# OBC_v1_rev_d.net
KiCad netlist of a schematic drawn in EAGLE
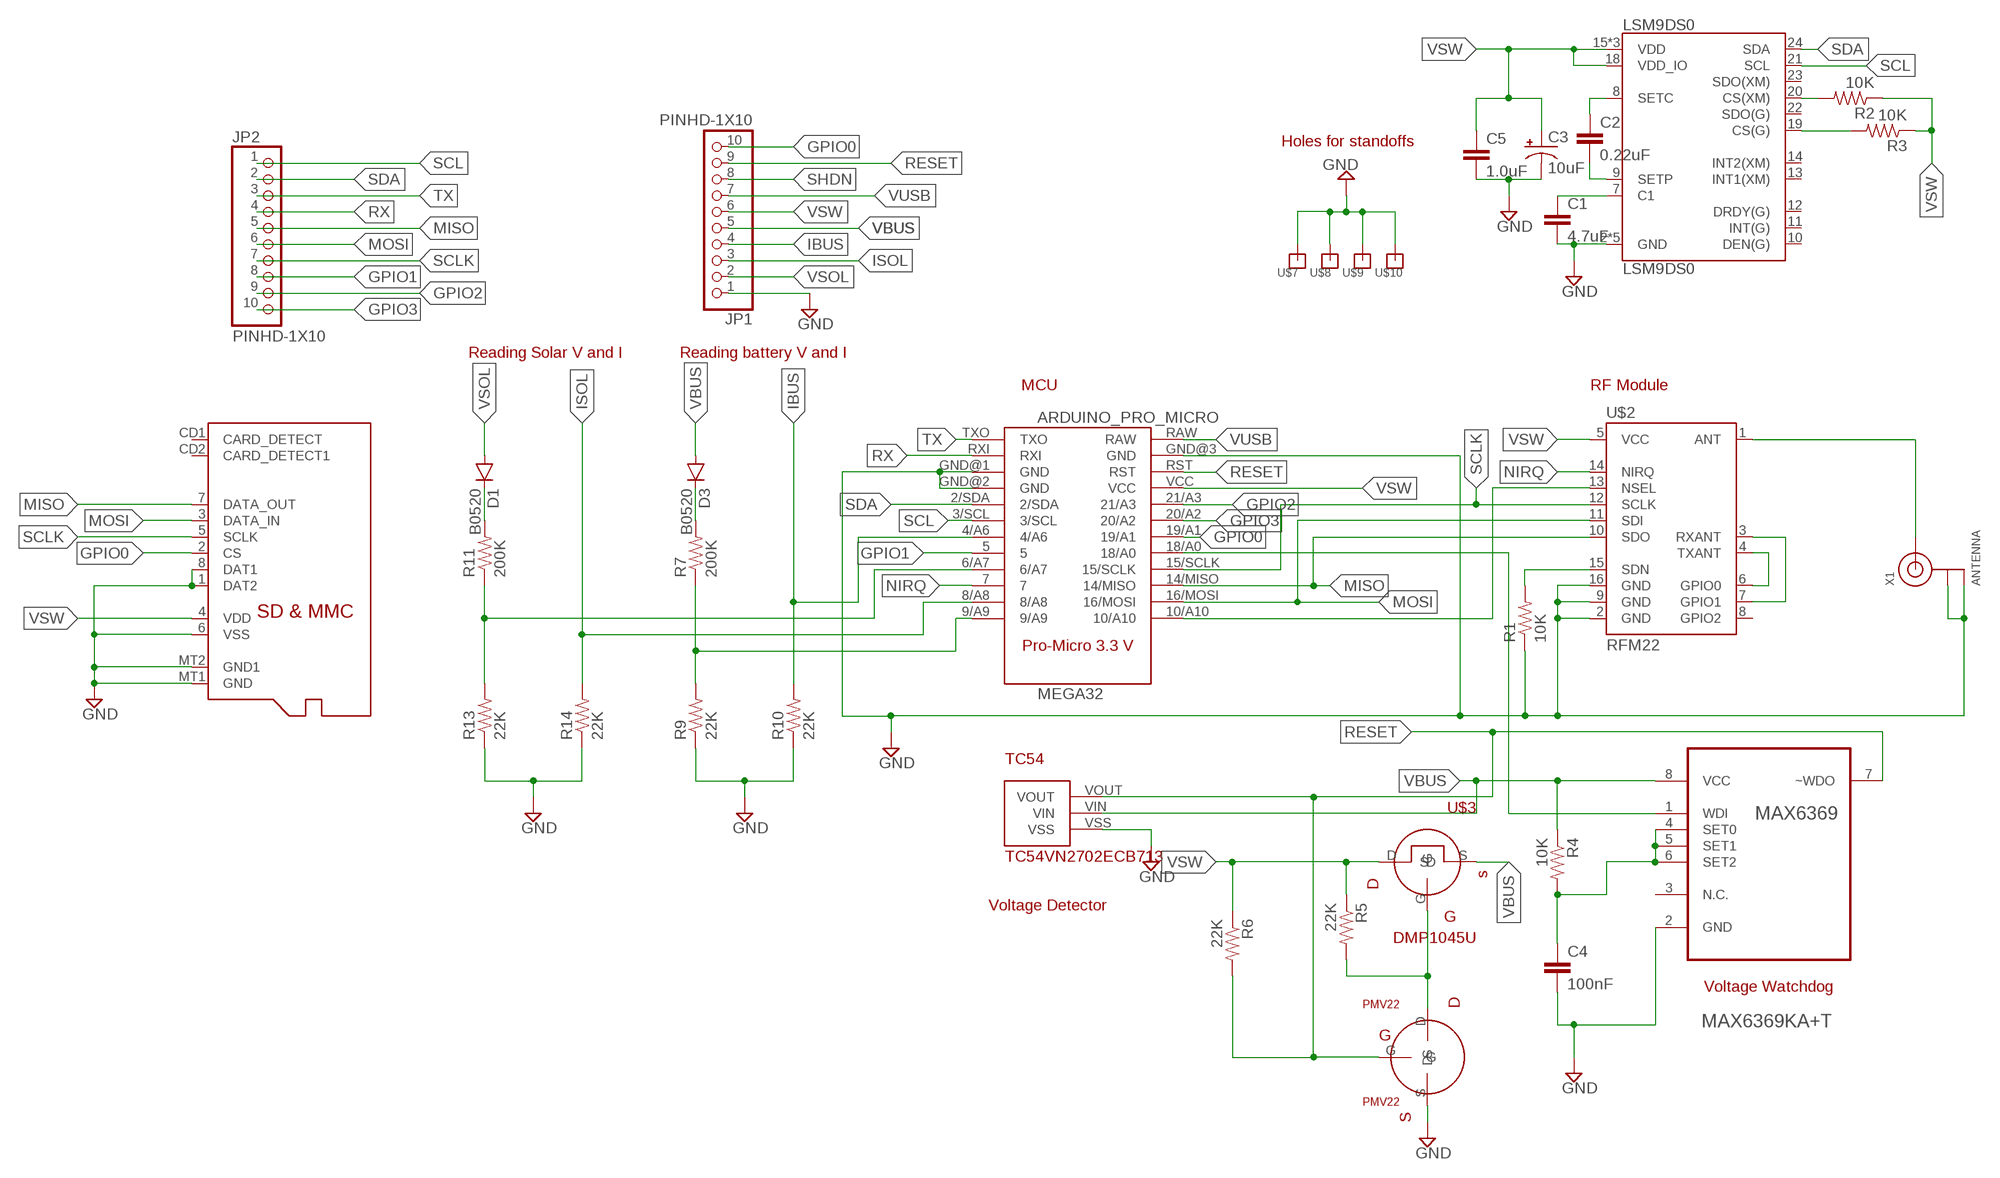
[diagram p0: schematic, sheet 1]

(export (version "E")
  (design (tool "Eeschema 10.0.6"))
  (components
    (comp (ref "ARDUINO_PRO_MICRO")
      (value "MEGA32")
      (footprint "eagle-import:MEGA32")
      (libsource (lib "eagle-import") (part "MEGA32"))
    )
    (comp (ref "C1")
      (value "4.7uF")
      (footprint "eagle-import:0402-CAP")
      (libsource (lib "eagle-import") (part "CAP0402-CAP"))
    )
    (comp (ref "C2")
      (value "0.22uF")
      (footprint "eagle-import:0402-CAP")
      (libsource (lib "eagle-import") (part "CAP0402-CAP"))
    )
    (comp (ref "C3")
      (value "10uF")
      (footprint "eagle-import:EIA3216")
      (libsource (lib "eagle-import") (part "CAP_POL1206"))
    )
    (comp (ref "C4")
      (value "100nF")
      (footprint "eagle-import:0402-CAP")
      (libsource (lib "eagle-import") (part "CAP0402-CAP"))
    )
    (comp (ref "C5")
      (value "1.0uF")
      (footprint "eagle-import:0402-CAP")
      (libsource (lib "eagle-import") (part "CAP0402-CAP"))
    )
    (comp (ref "D1")
      (value "B0520")
      (footprint "eagle-import:SOD-123")
      (libsource (lib "eagle-import") (part "DIODESOD123"))
    )
    (comp (ref "D3")
      (value "B0520")
      (footprint "eagle-import:SOD-123")
      (libsource (lib "eagle-import") (part "DIODESOD123"))
    )
    (comp (ref "JP1")
      (value "PINHD-1X10")
      (footprint "eagle-import:1X10-BIG")
      (libsource (lib "eagle-import") (part "PINHD-1X10"))
    )
    (comp (ref "JP2")
      (value "PINHD-1X10")
      (footprint "eagle-import:1X10-BIG")
      (libsource (lib "eagle-import") (part "PINHD-1X10"))
    )
    (comp (ref "LSM9DS0")
      (value "LSM9DS0")
      (footprint "eagle-import:LGA-24")
      (libsource (lib "eagle-import") (part "LSM9DS0"))
    )
    (comp (ref "MAX6369")
      (value "MAX6369KA+T")
      (footprint "eagle-import:SOT65P280X145-8N")
      (libsource (lib "eagle-import") (part "MAX6369KA+T"))
    )
    (comp (ref "PMV22")
      (value "PMV22")
      (footprint "eagle-import:PMV22")
      (libsource (lib "eagle-import") (part "PMV22"))
    )
    (comp (ref "R1")
      (value "10K")
      (footprint "eagle-import:0402-RES")
      (libsource (lib "eagle-import") (part "RESISTOR0402-RES"))
    )
    (comp (ref "R2")
      (value "10K")
      (footprint "eagle-import:0402-RES")
      (libsource (lib "eagle-import") (part "RESISTOR0402-RES"))
    )
    (comp (ref "R3")
      (value "10K")
      (footprint "eagle-import:0402-RES")
      (libsource (lib "eagle-import") (part "RESISTOR0402-RES"))
    )
    (comp (ref "R4")
      (value "10K")
      (footprint "eagle-import:0402-RES")
      (libsource (lib "eagle-import") (part "RESISTOR0402-RES"))
    )
    (comp (ref "R5")
      (value "22K")
      (footprint "eagle-import:0402-RES")
      (libsource (lib "eagle-import") (part "RESISTOR0402-RES"))
    )
    (comp (ref "R6")
      (value "22K")
      (footprint "eagle-import:0402-RES")
      (libsource (lib "eagle-import") (part "RESISTOR0402-RES"))
    )
    (comp (ref "R7")
      (value "200K")
      (footprint "eagle-import:0402-RES")
      (libsource (lib "eagle-import") (part "RESISTOR0402-RES"))
    )
    (comp (ref "R9")
      (value "22K")
      (footprint "eagle-import:0402-RES")
      (libsource (lib "eagle-import") (part "RESISTOR0402-RES"))
    )
    (comp (ref "R10")
      (value "22K")
      (footprint "eagle-import:0402-RES")
      (libsource (lib "eagle-import") (part "RESISTOR0402-RES"))
    )
    (comp (ref "R11")
      (value "200K")
      (footprint "eagle-import:0402-RES")
      (libsource (lib "eagle-import") (part "RESISTOR0402-RES"))
    )
    (comp (ref "R13")
      (value "22K")
      (footprint "eagle-import:0402-RES")
      (libsource (lib "eagle-import") (part "RESISTOR0402-RES"))
    )
    (comp (ref "R14")
      (value "22K")
      (footprint "eagle-import:0402-RES")
      (libsource (lib "eagle-import") (part "RESISTOR0402-RES"))
    )
    (comp (ref "TC54")
      (value "TC54VN2702ECB713")
      (footprint "eagle-import:TC54")
      (libsource (lib "eagle-import") (part "TC54"))
    )
    (comp (ref "U$2")
      (value "RFM22")
      (footprint "eagle-import:RFM22-XXX-S2")
      (libsource (lib "eagle-import") (part "RFM22SMD"))
    )
    (comp (ref "U$3")
      (value "DMP1045U")
      (footprint "eagle-import:DMP1045U")
      (libsource (lib "eagle-import") (part "DMP1045U"))
    )
    (comp (ref "U$7")
      (value "3MMPILAR")
      (footprint "eagle-import:3MMPILAR")
      (libsource (lib "eagle-import") (part "3MMPILAR"))
    )
    (comp (ref "U$8")
      (value "3MMPILAR")
      (footprint "eagle-import:3MMPILAR")
      (libsource (lib "eagle-import") (part "3MMPILAR"))
    )
    (comp (ref "U$9")
      (value "3MMPILAR")
      (footprint "eagle-import:3MMPILAR")
      (libsource (lib "eagle-import") (part "3MMPILAR"))
    )
    (comp (ref "U$10")
      (value "3MMPILAR")
      (footprint "eagle-import:3MMPILAR")
      (libsource (lib "eagle-import") (part "3MMPILAR"))
    )
    (comp (ref "X1")
      (value "ANTENNA")
      (footprint "eagle-import:U.FL")
      (libsource (lib "eagle-import") (part "ANTENNA_U.FL"))
    )
    (comp (ref "μSD")
      (value "MICROSD")
      (footprint "eagle-import:MICROSD")
      (libsource (lib "eagle-import") (part "MICROSD"))
    )
  )
  (nets
    (net (code "1") (name "GND") (class "Default")
      (node (ref "ARDUINO_PRO_MICRO") (pin "GND@1") (pinfunction "GND_GND@1") (pintype "bidirectional"))
      (node (ref "ARDUINO_PRO_MICRO") (pin "GND@2") (pinfunction "GND_GND@2") (pintype "bidirectional"))
      (node (ref "ARDUINO_PRO_MICRO") (pin "GND@3") (pinfunction "GND_GND@3") (pintype "bidirectional"))
      (node (ref "C1") (pin "2") (pinfunction "2_2") (pintype "passive"))
      (node (ref "C3") (pin "C") (pinfunction "-_C") (pintype "passive"))
      (node (ref "C4") (pin "2") (pinfunction "2_2") (pintype "passive"))
      (node (ref "C5") (pin "2") (pinfunction "2_2") (pintype "passive"))
      (node (ref "JP1") (pin "1") (pinfunction "1_1") (pintype "passive"))
      (node (ref "LSM9DS0") (pin "2") (pinfunction "GND_2") (pintype "bidirectional"))
      (node (ref "LSM9DS0") (pin "3") (pinfunction "GND_3") (pintype "bidirectional"))
      (node (ref "LSM9DS0") (pin "4") (pinfunction "GND_4") (pintype "bidirectional"))
      (node (ref "LSM9DS0") (pin "5") (pinfunction "GND_5") (pintype "bidirectional"))
      (node (ref "LSM9DS0") (pin "6") (pinfunction "GND_6") (pintype "bidirectional"))
      (node (ref "MAX6369") (pin "2") (pinfunction "GND_2") (pintype "passive"))
      (node (ref "PMV22") (pin "S") (pinfunction "S_S") (pintype "bidirectional"))
      (node (ref "R1") (pin "1") (pinfunction "1_1") (pintype "passive"))
      (node (ref "R10") (pin "1") (pinfunction "1_1") (pintype "passive"))
      (node (ref "R13") (pin "1") (pinfunction "1_1") (pintype "passive"))
      (node (ref "R14") (pin "1") (pinfunction "1_1") (pintype "passive"))
      (node (ref "R9") (pin "1") (pinfunction "1_1") (pintype "passive"))
      (node (ref "TC54") (pin "VSS") (pinfunction "VSS_VSS") (pintype "bidirectional"))
      (node (ref "U$10") (pin "P$1") (pinfunction "P$1_P$1") (pintype "bidirectional"))
      (node (ref "U$2") (pin "16") (pinfunction "GND_16") (pintype "power_in"))
      (node (ref "U$2") (pin "2") (pinfunction "GND_2") (pintype "power_in"))
      (node (ref "U$2") (pin "9") (pinfunction "GND_9") (pintype "power_in"))
      (node (ref "U$7") (pin "P$1") (pinfunction "P$1_P$1") (pintype "bidirectional"))
      (node (ref "U$8") (pin "P$1") (pinfunction "P$1_P$1") (pintype "bidirectional"))
      (node (ref "U$9") (pin "P$1") (pinfunction "P$1_P$1") (pintype "bidirectional"))
      (node (ref "X1") (pin "1") (pinfunction "GND_1") (pintype "passive"))
      (node (ref "X1") (pin "2") (pinfunction "GND_2") (pintype "passive"))
      (node (ref "μSD") (pin "1") (pinfunction "DAT2_1") (pintype "bidirectional"))
      (node (ref "μSD") (pin "6") (pinfunction "VSS_6") (pintype "power_in"))
      (node (ref "μSD") (pin "8") (pinfunction "DAT1_8") (pintype "bidirectional"))
      (node (ref "μSD") (pin "MT1") (pinfunction "GND_MT1") (pintype "power_in"))
      (node (ref "μSD") (pin "MT2") (pinfunction "GND1_MT2") (pintype "power_in"))
    )
    (net (code "2") (name "GPIO0") (class "Default")
      (node (ref "ARDUINO_PRO_MICRO") (pin "19/A1") (pinfunction "19/A1_19/A1") (pintype "bidirectional"))
      (node (ref "JP1") (pin "10") (pinfunction "10_10") (pintype "passive"))
      (node (ref "μSD") (pin "2") (pinfunction "CS_2") (pintype "input"))
    )
    (net (code "3") (name "GPIO1") (class "Default")
      (node (ref "ARDUINO_PRO_MICRO") (pin "5") (pinfunction "5_5") (pintype "bidirectional"))
      (node (ref "JP2") (pin "8") (pinfunction "8_8") (pintype "passive"))
    )
    (net (code "4") (name "GPIO2") (class "Default")
      (node (ref "ARDUINO_PRO_MICRO") (pin "21/A3") (pinfunction "21/A3_21/A3") (pintype "bidirectional"))
      (node (ref "JP2") (pin "9") (pinfunction "9_9") (pintype "passive"))
    )
    (net (code "5") (name "GPIO3") (class "Default")
      (node (ref "ARDUINO_PRO_MICRO") (pin "20/A2") (pinfunction "20/A2_20/A2") (pintype "bidirectional"))
      (node (ref "JP2") (pin "10") (pinfunction "10_10") (pintype "passive"))
    )
    (net (code "6") (name "IBUS") (class "Default")
      (node (ref "ARDUINO_PRO_MICRO") (pin "4/A6") (pinfunction "4/A6_4/A6") (pintype "bidirectional"))
      (node (ref "JP1") (pin "4") (pinfunction "4_4") (pintype "passive"))
      (node (ref "R10") (pin "2") (pinfunction "2_2") (pintype "passive"))
    )
    (net (code "7") (name "ISOL") (class "Default")
      (node (ref "ARDUINO_PRO_MICRO") (pin "8/A8") (pinfunction "8/A8_8/A8") (pintype "bidirectional"))
      (node (ref "JP1") (pin "3") (pinfunction "3_3") (pintype "passive"))
      (node (ref "R14") (pin "2") (pinfunction "2_2") (pintype "passive"))
    )
    (net (code "8") (name "MISO") (class "Default")
      (node (ref "ARDUINO_PRO_MICRO") (pin "14/MISO") (pinfunction "14/MISO_14/MISO") (pintype "bidirectional"))
      (node (ref "JP2") (pin "5") (pinfunction "5_5") (pintype "passive"))
      (node (ref "U$2") (pin "10") (pinfunction "SDO_10") (pintype "output"))
      (node (ref "μSD") (pin "7") (pinfunction "DATA_OUT_7") (pintype "output"))
    )
    (net (code "9") (name "MOSI") (class "Default")
      (node (ref "ARDUINO_PRO_MICRO") (pin "16/MOSI") (pinfunction "16/MOSI_16/MOSI") (pintype "bidirectional"))
      (node (ref "JP2") (pin "6") (pinfunction "6_6") (pintype "passive"))
      (node (ref "U$2") (pin "11") (pinfunction "SDI_11") (pintype "input"))
      (node (ref "μSD") (pin "3") (pinfunction "DATA_IN_3") (pintype "input"))
    )
    (net (code "10") (name "NIRQ") (class "Default")
      (node (ref "ARDUINO_PRO_MICRO") (pin "7") (pinfunction "7_7") (pintype "bidirectional"))
      (node (ref "U$2") (pin "14") (pinfunction "NIRQ_14") (pintype "output"))
    )
    (net (code "11") (name "Net-(ARDUINO_PRO_MICRO-Pad6{slash}A7)") (class "Default")
      (node (ref "ARDUINO_PRO_MICRO") (pin "6/A7") (pinfunction "6/A7_6/A7") (pintype "bidirectional"))
      (node (ref "R11") (pin "1") (pinfunction "1_1") (pintype "passive"))
      (node (ref "R13") (pin "2") (pinfunction "2_2") (pintype "passive"))
    )
    (net (code "12") (name "Net-(ARDUINO_PRO_MICRO-Pad9{slash}A9)") (class "Default")
      (node (ref "ARDUINO_PRO_MICRO") (pin "9/A9") (pinfunction "9/A9_9/A9") (pintype "bidirectional"))
      (node (ref "R7") (pin "1") (pinfunction "1_1") (pintype "passive"))
      (node (ref "R9") (pin "2") (pinfunction "2_2") (pintype "passive"))
    )
    (net (code "13") (name "Net-(D1-PadC)") (class "Default")
      (node (ref "D1") (pin "C") (pinfunction "C_C") (pintype "passive"))
      (node (ref "R11") (pin "2") (pinfunction "2_2") (pintype "passive"))
    )
    (net (code "14") (name "Net-(D3-PadC)") (class "Default")
      (node (ref "D3") (pin "C") (pinfunction "C_C") (pintype "passive"))
      (node (ref "R7") (pin "2") (pinfunction "2_2") (pintype "passive"))
    )
    (net (code "15") (name "Net-(LSM9DS0-C1)") (class "Default")
      (node (ref "C1") (pin "1") (pinfunction "1_1") (pintype "passive"))
      (node (ref "LSM9DS0") (pin "7") (pinfunction "C1_7") (pintype "bidirectional"))
    )
    (net (code "16") (name "Net-(LSM9DS0-CS(G))") (class "Default")
      (node (ref "LSM9DS0") (pin "19") (pinfunction "CS(G)_19") (pintype "bidirectional"))
      (node (ref "R3") (pin "2") (pinfunction "2_2") (pintype "passive"))
    )
    (net (code "17") (name "Net-(LSM9DS0-CS(XM))") (class "Default")
      (node (ref "LSM9DS0") (pin "20") (pinfunction "CS(XM)_20") (pintype "bidirectional"))
      (node (ref "R2") (pin "2") (pinfunction "2_2") (pintype "passive"))
    )
    (net (code "18") (name "Net-(LSM9DS0-SETC)") (class "Default")
      (node (ref "C2") (pin "1") (pinfunction "1_1") (pintype "passive"))
      (node (ref "LSM9DS0") (pin "8") (pinfunction "SETC_8") (pintype "bidirectional"))
    )
    (net (code "19") (name "Net-(LSM9DS0-SETP)") (class "Default")
      (node (ref "C2") (pin "2") (pinfunction "2_2") (pintype "passive"))
      (node (ref "LSM9DS0") (pin "9") (pinfunction "SETP_9") (pintype "bidirectional"))
    )
    (net (code "20") (name "Net-(MAX6369-SET0)") (class "Default")
      (node (ref "C4") (pin "1") (pinfunction "1_1") (pintype "passive"))
      (node (ref "MAX6369") (pin "4") (pinfunction "SET0_4") (pintype "input"))
      (node (ref "MAX6369") (pin "5") (pinfunction "SET1_5") (pintype "input"))
      (node (ref "MAX6369") (pin "6") (pinfunction "SET2_6") (pintype "input"))
      (node (ref "R4") (pin "2") (pinfunction "2_2") (pintype "passive"))
    )
    (net (code "21") (name "Net-(MAX6369-WDI)") (class "Default")
      (node (ref "ARDUINO_PRO_MICRO") (pin "18/A0") (pinfunction "18/A0_18/A0") (pintype "bidirectional"))
      (node (ref "MAX6369") (pin "1") (pinfunction "WDI_1") (pintype "input"))
    )
    (net (code "22") (name "Net-(PMV22-PadD)") (class "Default")
      (node (ref "PMV22") (pin "D") (pinfunction "D_D") (pintype "bidirectional"))
      (node (ref "R5") (pin "2") (pinfunction "2_2") (pintype "passive"))
      (node (ref "U$3") (pin "G") (pinfunction "G_G") (pintype "bidirectional"))
    )
    (net (code "23") (name "Net-(U$2-ANT)") (class "Default")
      (node (ref "U$2") (pin "1") (pinfunction "ANT_1") (pintype "bidirectional"))
      (node (ref "X1") (pin "3") (pinfunction "SIGNAL_3") (pintype "passive"))
    )
    (net (code "24") (name "Net-(U$2-GPIO0)") (class "Default")
      (node (ref "U$2") (pin "4") (pinfunction "TXANT_4") (pintype "input"))
      (node (ref "U$2") (pin "6") (pinfunction "GPIO0_6") (pintype "bidirectional"))
    )
    (net (code "25") (name "Net-(U$2-GPIO1)") (class "Default")
      (node (ref "U$2") (pin "3") (pinfunction "RXANT_3") (pintype "input"))
      (node (ref "U$2") (pin "7") (pinfunction "GPIO1_7") (pintype "bidirectional"))
    )
    (net (code "26") (name "Net-(U$2-NSEL)") (class "Default")
      (node (ref "ARDUINO_PRO_MICRO") (pin "10/A10") (pinfunction "10/A10_10/A10") (pintype "bidirectional"))
      (node (ref "U$2") (pin "13") (pinfunction "NSEL_13") (pintype "input"))
    )
    (net (code "27") (name "Net-(U$2-SDN)") (class "Default")
      (node (ref "R1") (pin "2") (pinfunction "2_2") (pintype "passive"))
      (node (ref "U$2") (pin "15") (pinfunction "SDN_15") (pintype "input"))
    )
    (net (code "28") (name "RESET") (class "Default")
      (node (ref "ARDUINO_PRO_MICRO") (pin "RST") (pinfunction "RST_RST") (pintype "bidirectional"))
      (node (ref "JP1") (pin "9") (pinfunction "9_9") (pintype "passive"))
      (node (ref "MAX6369") (pin "7") (pinfunction "~{WDO}_7") (pintype "output"))
      (node (ref "PMV22") (pin "G") (pinfunction "G_G") (pintype "bidirectional"))
      (node (ref "R6") (pin "2") (pinfunction "2_2") (pintype "passive"))
      (node (ref "TC54") (pin "VOUT") (pinfunction "VOUT_VOUT") (pintype "bidirectional"))
    )
    (net (code "29") (name "RX") (class "Default")
      (node (ref "ARDUINO_PRO_MICRO") (pin "RXI") (pinfunction "RXI_RXI") (pintype "bidirectional"))
      (node (ref "JP2") (pin "4") (pinfunction "4_4") (pintype "passive"))
    )
    (net (code "30") (name "SCL") (class "Default")
      (node (ref "ARDUINO_PRO_MICRO") (pin "3/SCL") (pinfunction "3/SCL_3/SCL") (pintype "bidirectional"))
      (node (ref "JP2") (pin "1") (pinfunction "1_1") (pintype "passive"))
      (node (ref "LSM9DS0") (pin "21") (pinfunction "SCL_21") (pintype "bidirectional"))
    )
    (net (code "31") (name "SCLK") (class "Default")
      (node (ref "ARDUINO_PRO_MICRO") (pin "15/SCLK") (pinfunction "15/SCLK_15/SCLK") (pintype "bidirectional"))
      (node (ref "JP2") (pin "7") (pinfunction "7_7") (pintype "passive"))
      (node (ref "U$2") (pin "12") (pinfunction "SCLK_12") (pintype "input"))
      (node (ref "μSD") (pin "5") (pinfunction "SCLK_5") (pintype "input"))
    )
    (net (code "32") (name "SDA") (class "Default")
      (node (ref "ARDUINO_PRO_MICRO") (pin "2/SDA") (pinfunction "2/SDA_2/SDA") (pintype "bidirectional"))
      (node (ref "JP2") (pin "2") (pinfunction "2_2") (pintype "passive"))
      (node (ref "LSM9DS0") (pin "24") (pinfunction "SDA_24") (pintype "bidirectional"))
    )
    (net (code "33") (name "SHDN") (class "Default")
      (node (ref "JP1") (pin "8") (pinfunction "8_8") (pintype "passive"))
    )
    (net (code "34") (name "TX") (class "Default")
      (node (ref "ARDUINO_PRO_MICRO") (pin "TXO") (pinfunction "TXO_TXO") (pintype "bidirectional"))
      (node (ref "JP2") (pin "3") (pinfunction "3_3") (pintype "passive"))
    )
    (net (code "35") (name "VBUS") (class "Default")
      (node (ref "D3") (pin "A") (pinfunction "A_A") (pintype "passive"))
      (node (ref "JP1") (pin "5") (pinfunction "5_5") (pintype "passive"))
      (node (ref "MAX6369") (pin "8") (pinfunction "VCC_8") (pintype "power_in"))
      (node (ref "R4") (pin "1") (pinfunction "1_1") (pintype "passive"))
      (node (ref "TC54") (pin "VIN") (pinfunction "VIN_VIN") (pintype "bidirectional"))
      (node (ref "U$3") (pin "S") (pinfunction "S_S") (pintype "bidirectional"))
    )
    (net (code "36") (name "VSOL") (class "Default")
      (node (ref "D1") (pin "A") (pinfunction "A_A") (pintype "passive"))
      (node (ref "JP1") (pin "2") (pinfunction "2_2") (pintype "passive"))
    )
    (net (code "37") (name "VSW") (class "Default")
      (node (ref "ARDUINO_PRO_MICRO") (pin "VCC") (pinfunction "VCC_VCC") (pintype "bidirectional"))
      (node (ref "C3") (pin "A") (pinfunction "+_A") (pintype "passive"))
      (node (ref "C5") (pin "1") (pinfunction "1_1") (pintype "passive"))
      (node (ref "JP1") (pin "6") (pinfunction "6_6") (pintype "passive"))
      (node (ref "LSM9DS0") (pin "15") (pinfunction "VDD_15") (pintype "bidirectional"))
      (node (ref "LSM9DS0") (pin "16") (pinfunction "VDD_16") (pintype "bidirectional"))
      (node (ref "LSM9DS0") (pin "17") (pinfunction "VDD_17") (pintype "bidirectional"))
      (node (ref "LSM9DS0") (pin "18") (pinfunction "VDD_IO_18") (pintype "bidirectional"))
      (node (ref "R2") (pin "1") (pinfunction "1_1") (pintype "passive"))
      (node (ref "R3") (pin "1") (pinfunction "1_1") (pintype "passive"))
      (node (ref "R5") (pin "1") (pinfunction "1_1") (pintype "passive"))
      (node (ref "R6") (pin "1") (pinfunction "1_1") (pintype "passive"))
      (node (ref "U$2") (pin "5") (pinfunction "VCC_5") (pintype "bidirectional"))
      (node (ref "U$3") (pin "D") (pinfunction "D_D") (pintype "bidirectional"))
      (node (ref "μSD") (pin "4") (pinfunction "VDD_4") (pintype "power_in"))
    )
    (net (code "38") (name "VUSB") (class "Default")
      (node (ref "ARDUINO_PRO_MICRO") (pin "RAW") (pinfunction "RAW_RAW") (pintype "bidirectional"))
      (node (ref "JP1") (pin "7") (pinfunction "7_7") (pintype "passive"))
    )
    (net (code "39") (name "unconnected-(LSM9DS0-DEN(G)-Pad10)") (class "Default")
      (node (ref "LSM9DS0") (pin "10") (pinfunction "DEN(G)_10") (pintype "bidirectional"))
    )
    (net (code "40") (name "unconnected-(LSM9DS0-DRDY(G)-Pad12)") (class "Default")
      (node (ref "LSM9DS0") (pin "12") (pinfunction "DRDY(G)_12") (pintype "bidirectional"))
    )
    (net (code "41") (name "unconnected-(LSM9DS0-INT(G)-Pad11)") (class "Default")
      (node (ref "LSM9DS0") (pin "11") (pinfunction "INT(G)_11") (pintype "bidirectional"))
    )
    (net (code "42") (name "unconnected-(LSM9DS0-INT1(XM)-Pad13)") (class "Default")
      (node (ref "LSM9DS0") (pin "13") (pinfunction "INT1(XM)_13") (pintype "bidirectional"))
    )
    (net (code "43") (name "unconnected-(LSM9DS0-INT2(XM)-Pad14)") (class "Default")
      (node (ref "LSM9DS0") (pin "14") (pinfunction "INT2(XM)_14") (pintype "bidirectional"))
    )
    (net (code "44") (name "unconnected-(LSM9DS0-SDO(G)-Pad22)") (class "Default")
      (node (ref "LSM9DS0") (pin "22") (pinfunction "SDO(G)_22") (pintype "bidirectional"))
    )
    (net (code "45") (name "unconnected-(LSM9DS0-SDO(XM)-Pad23)") (class "Default")
      (node (ref "LSM9DS0") (pin "23") (pinfunction "SDO(XM)_23") (pintype "bidirectional"))
    )
    (net (code "46") (name "unconnected-(MAX6369-N.C.-Pad3)") (class "Default")
      (node (ref "MAX6369") (pin "3") (pinfunction "N.C._3") (pintype "no_connect"))
    )
    (net (code "47") (name "unconnected-(U$2-GPIO2-Pad8)") (class "Default")
      (node (ref "U$2") (pin "8") (pinfunction "GPIO2_8") (pintype "bidirectional"))
    )
    (net (code "48") (name "unconnected-(μSD-CARD_DETECT-PadCD1)") (class "Default")
      (node (ref "μSD") (pin "CD1") (pinfunction "CARD_DETECT_CD1") (pintype "passive"))
    )
    (net (code "49") (name "unconnected-(μSD-CARD_DETECT1-PadCD2)") (class "Default")
      (node (ref "μSD") (pin "CD2") (pinfunction "CARD_DETECT1_CD2") (pintype "passive"))
    )
  )
)
